# nomcu.net
KiCad netlist of a schematic drawn in EAGLE
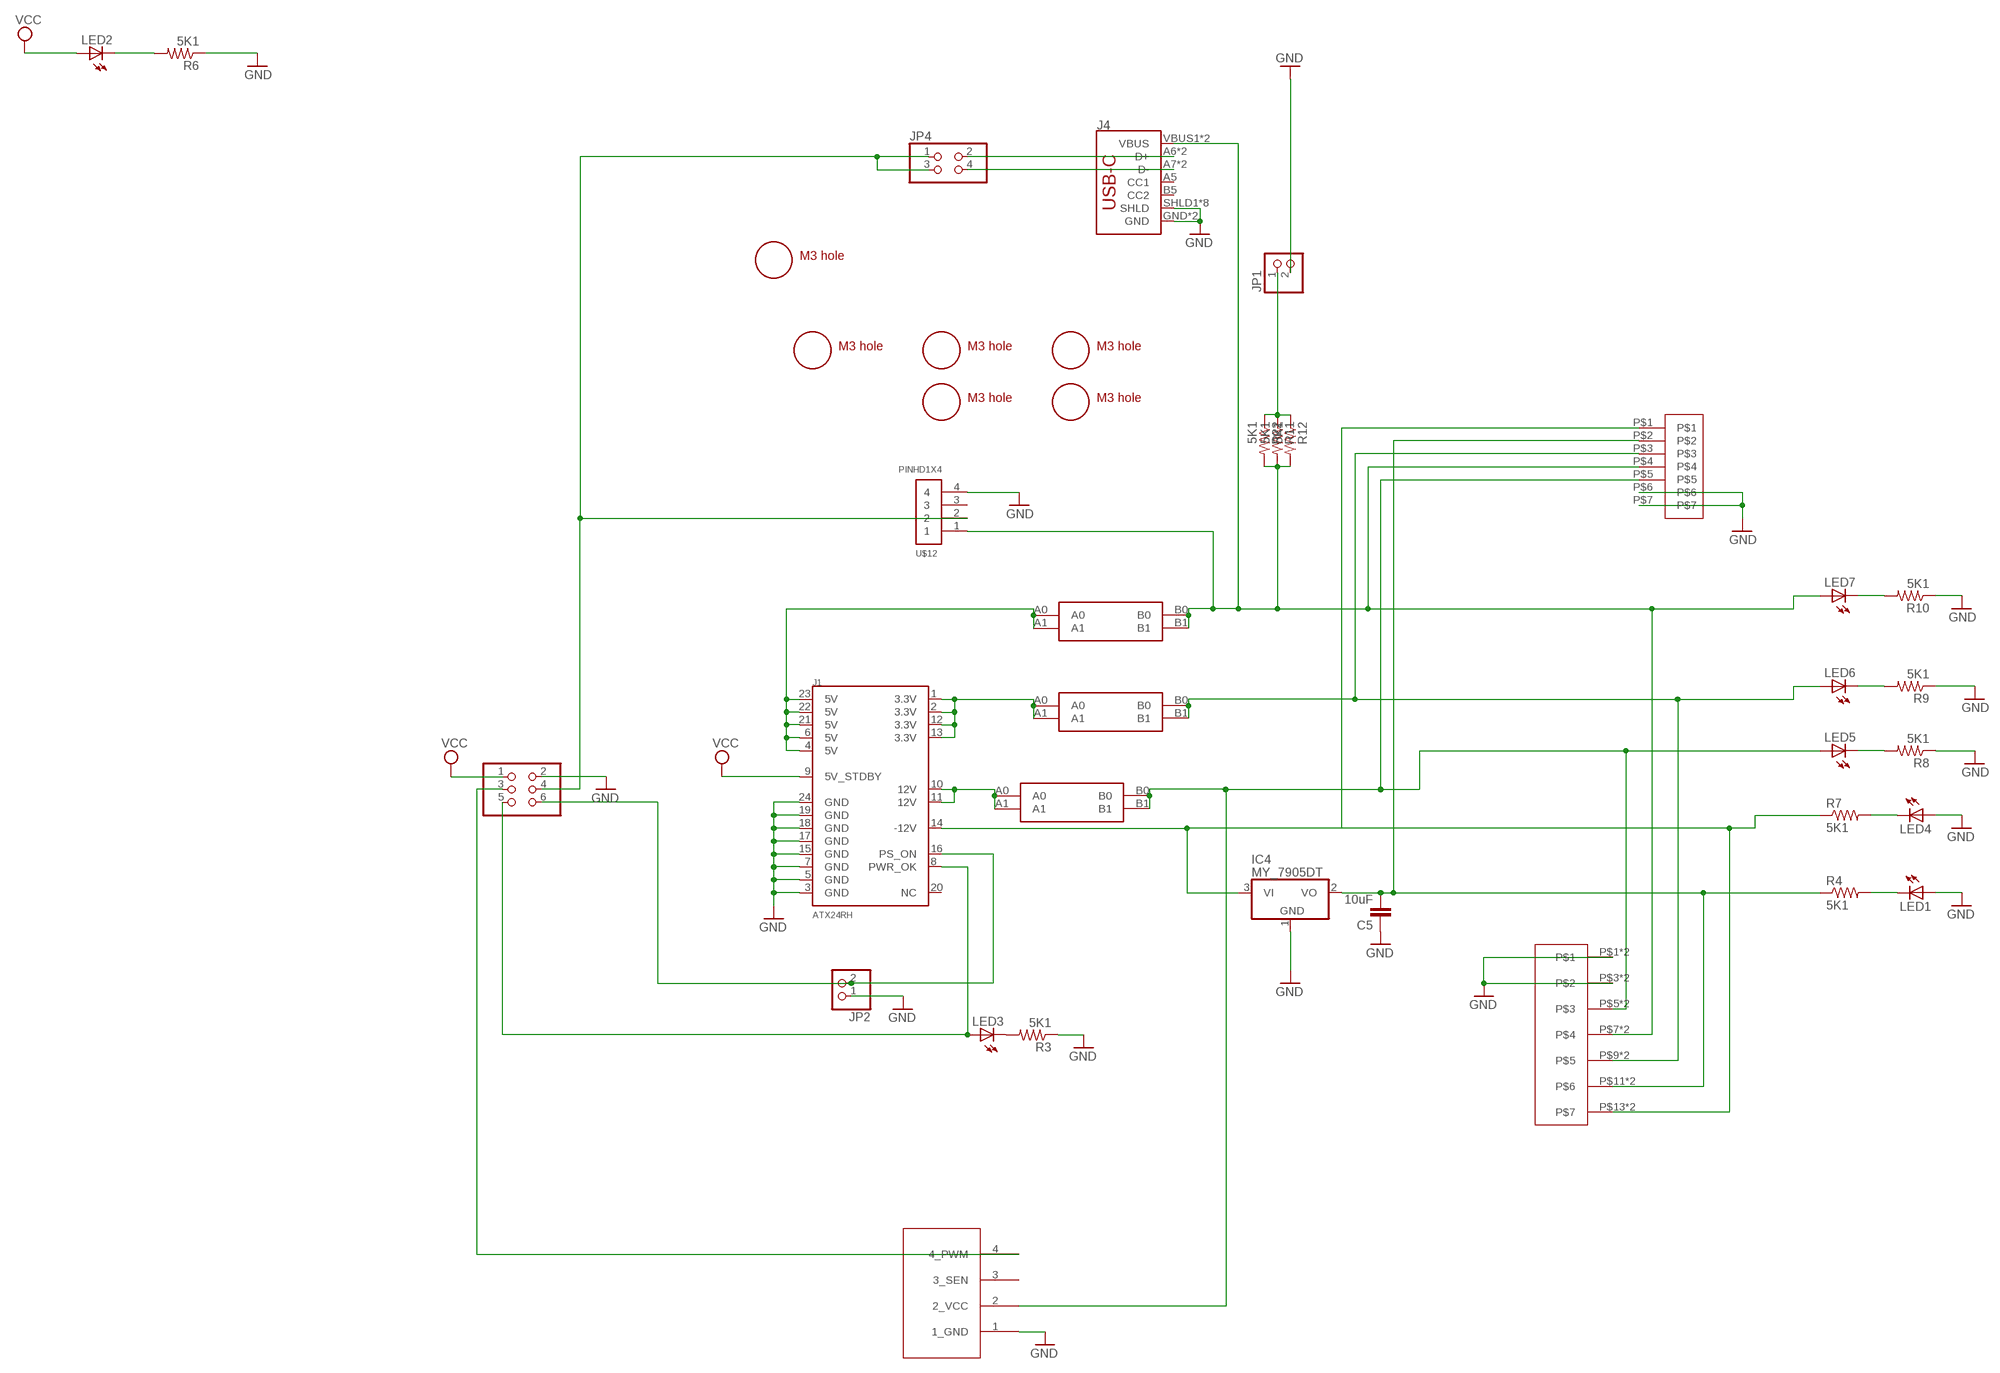
[diagram p0: schematic, sheet 1]

(export (version "E")
  (design (tool "Eeschema 10.0.6"))
  (components
    (comp (ref "C5")
      (value "10uF")
      (footprint "eagle-import:0805$1")
      (libsource (lib "eagle-import") (part "CAP0805"))
    )
    (comp (ref "IC4")
      (value "MY_7905DT")
      (footprint "eagle-import:ADAFRUIT_TO252")
      (libsource (lib "eagle-import") (part "MY_7905DT"))
    )
    (comp (ref "J1")
      (value "ATX24RH")
      (footprint "eagle-import:ATX24_RIGHT_ANGLE")
      (libsource (lib "eagle-import") (part "ATX24RH"))
    )
    (comp (ref "J4")
      (value "USB_C16PIN")
      (footprint "eagle-import:USB-C-16P")
      (libsource (lib "eagle-import") (part "USB_C16PIN"))
    )
    (comp (ref "JP1")
      (value "PINHD-1X2")
      (footprint "eagle-import:1X02")
      (libsource (lib "eagle-import") (part "PINHD-1X2"))
    )
    (comp (ref "JP2")
      (value "PINHD-1X2")
      (footprint "eagle-import:1X02")
      (libsource (lib "eagle-import") (part "PINHD-1X2"))
    )
    (comp (ref "JP3")
      (value "PINHD-2X3")
      (footprint "eagle-import:2X03")
      (libsource (lib "eagle-import") (part "PINHD-2X3"))
    )
    (comp (ref "JP4")
      (value "PINHD-2X2")
      (footprint "eagle-import:2X02")
      (libsource (lib "eagle-import") (part "PINHD-2X2"))
    )
    (comp (ref "JP8")
      (value "4PIN_FAN")
      (footprint "eagle-import:1X04")
      (libsource (lib "eagle-import") (part "4PIN_FAN"))
    )
    (comp (ref "LED1")
      (value "LEDCHIP-LED0805")
      (footprint "eagle-import:CHIP-LED0805")
      (libsource (lib "eagle-import") (part "LEDCHIP-LED0805"))
    )
    (comp (ref "LED2")
      (value "LEDCHIP-LED0805")
      (footprint "eagle-import:CHIP-LED0805")
      (libsource (lib "eagle-import") (part "LEDCHIP-LED0805"))
    )
    (comp (ref "LED3")
      (value "LEDCHIP-LED0805")
      (footprint "eagle-import:CHIP-LED0805")
      (libsource (lib "eagle-import") (part "LEDCHIP-LED0805"))
    )
    (comp (ref "LED4")
      (value "LEDCHIP-LED0805")
      (footprint "eagle-import:CHIP-LED0805")
      (libsource (lib "eagle-import") (part "LEDCHIP-LED0805"))
    )
    (comp (ref "LED5")
      (value "LEDCHIP-LED0805")
      (footprint "eagle-import:CHIP-LED0805")
      (libsource (lib "eagle-import") (part "LEDCHIP-LED0805"))
    )
    (comp (ref "LED6")
      (value "LEDCHIP-LED0805")
      (footprint "eagle-import:CHIP-LED0805")
      (libsource (lib "eagle-import") (part "LEDCHIP-LED0805"))
    )
    (comp (ref "LED7")
      (value "LEDCHIP-LED0805")
      (footprint "eagle-import:CHIP-LED0805")
      (libsource (lib "eagle-import") (part "LEDCHIP-LED0805"))
    )
    (comp (ref "R3")
      (value "5K1")
      (footprint "eagle-import:0805")
      (libsource (lib "eagle-import") (part "atx_power_control_RESISTOR0805-RES"))
    )
    (comp (ref "R4")
      (value "5K1")
      (footprint "eagle-import:0805")
      (libsource (lib "eagle-import") (part "RESISTOR0805-RES"))
    )
    (comp (ref "R6")
      (value "5K1")
      (footprint "eagle-import:0805")
      (libsource (lib "eagle-import") (part "atx_power_control_RESISTOR0805-RES"))
    )
    (comp (ref "R7")
      (value "5K1")
      (footprint "eagle-import:0805")
      (libsource (lib "eagle-import") (part "RESISTOR0805-RES"))
    )
    (comp (ref "R8")
      (value "5K1")
      (footprint "eagle-import:0805")
      (libsource (lib "eagle-import") (part "atx_power_control_RESISTOR0805-RES"))
    )
    (comp (ref "R9")
      (value "5K1")
      (footprint "eagle-import:0805")
      (libsource (lib "eagle-import") (part "atx_power_control_RESISTOR0805-RES"))
    )
    (comp (ref "R10")
      (value "5K1")
      (footprint "eagle-import:0805")
      (libsource (lib "eagle-import") (part "atx_power_control_RESISTOR0805-RES"))
    )
    (comp (ref "R11")
      (value "5K1")
      (footprint "eagle-import:0805")
      (libsource (lib "eagle-import") (part "atx_power_control_RESISTOR0805-RES"))
    )
    (comp (ref "R12")
      (value "5K1")
      (footprint "eagle-import:0805")
      (libsource (lib "eagle-import") (part "atx_power_control_RESISTOR0805-RES"))
    )
    (comp (ref "R22")
      (value "5K1")
      (footprint "eagle-import:0805")
      (libsource (lib "eagle-import") (part "atx_power_control_RESISTOR0805-RES"))
    )
    (comp (ref "U$1")
      (value "M3_MOUNTING_HOLE")
      (footprint "eagle-import:M3_MOUNTING_HOLE_PACK")
      (libsource (lib "eagle-import") (part "M3_MOUNTING_HOLE"))
    )
    (comp (ref "U$2")
      (value "M3_MOUNTING_HOLE")
      (footprint "eagle-import:M3_MOUNTING_HOLE_PACK")
      (libsource (lib "eagle-import") (part "M3_MOUNTING_HOLE"))
    )
    (comp (ref "U$3")
      (value "M3_MOUNTING_HOLE")
      (footprint "eagle-import:M3_MOUNTING_HOLE_PACK")
      (libsource (lib "eagle-import") (part "M3_MOUNTING_HOLE"))
    )
    (comp (ref "U$4")
      (value "VH396")
      (footprint "eagle-import:396_7P")
      (libsource (lib "eagle-import") (part "VH396"))
    )
    (comp (ref "U$5")
      (value "CAR_FUSE_HOLDER3IN1")
      (footprint "eagle-import:FUSE_HOLDER_3IN1")
      (libsource (lib "eagle-import") (part "CAR_FUSE_HOLDER3IN1"))
    )
    (comp (ref "U$6")
      (value "M3_MOUNTING_HOLE")
      (footprint "eagle-import:M3_MOUNTING_HOLE_PACK")
      (libsource (lib "eagle-import") (part "M3_MOUNTING_HOLE"))
    )
    (comp (ref "U$7")
      (value "CAR_FUSE_HOLDER3IN1")
      (footprint "eagle-import:FUSE_HOLDER_3IN1")
      (libsource (lib "eagle-import") (part "CAR_FUSE_HOLDER3IN1"))
    )
    (comp (ref "U$8")
      (value "CAR_FUSE_HOLDER3IN1")
      (footprint "eagle-import:FUSE_HOLDER_3IN1")
      (libsource (lib "eagle-import") (part "CAR_FUSE_HOLDER3IN1"))
    )
    (comp (ref "U$9")
      (value "DG2204R-5.0")
      (footprint "eagle-import:DG2204R")
      (libsource (lib "eagle-import") (part "DG2204R-5.0"))
    )
    (comp (ref "U$10")
      (value "M3_MOUNTING_HOLE")
      (footprint "eagle-import:M3_MOUNTING_HOLE_PACK")
      (libsource (lib "eagle-import") (part "M3_MOUNTING_HOLE"))
    )
    (comp (ref "U$11")
      (value "M3_MOUNTING_HOLE")
      (footprint "eagle-import:M3_MOUNTING_HOLE_PACK")
      (libsource (lib "eagle-import") (part "M3_MOUNTING_HOLE"))
    )
    (comp (ref "U$12")
      (value "PINHD1X4")
      (footprint "eagle-import:1X04-CLEANBIG")
      (libsource (lib "eagle-import") (part "PINHD1X4"))
    )
  )
  (nets
    (net (code "1") (name "GND") (class "Default")
      (node (ref "C5") (pin "1") (pinfunction "1_1") (pintype "passive"))
      (node (ref "IC4") (pin "1") (pinfunction "GND_1") (pintype "passive"))
      (node (ref "J1") (pin "15") (pinfunction "GND_15") (pintype "bidirectional"))
      (node (ref "J1") (pin "17") (pinfunction "GND_17") (pintype "bidirectional"))
      (node (ref "J1") (pin "18") (pinfunction "GND_18") (pintype "bidirectional"))
      (node (ref "J1") (pin "19") (pinfunction "GND_19") (pintype "bidirectional"))
      (node (ref "J1") (pin "24") (pinfunction "GND_24") (pintype "bidirectional"))
      (node (ref "J1") (pin "3") (pinfunction "GND_3") (pintype "bidirectional"))
      (node (ref "J1") (pin "5") (pinfunction "GND_5") (pintype "bidirectional"))
      (node (ref "J1") (pin "7") (pinfunction "GND_7") (pintype "bidirectional"))
      (node (ref "J4") (pin "GND") (pinfunction "GND_GND") (pintype "bidirectional"))
      (node (ref "J4") (pin "GND2") (pinfunction "GND_GND2") (pintype "bidirectional"))
      (node (ref "J4") (pin "SHLD1") (pinfunction "SHLD_SHLD1") (pintype "bidirectional"))
      (node (ref "J4") (pin "SHLD2") (pinfunction "SHLD_SHLD2") (pintype "bidirectional"))
      (node (ref "J4") (pin "SHLD3") (pinfunction "SHLD_SHLD3") (pintype "bidirectional"))
      (node (ref "J4") (pin "SHLD4") (pinfunction "SHLD_SHLD4") (pintype "bidirectional"))
      (node (ref "J4") (pin "SHLD5") (pinfunction "SHLD_SHLD5") (pintype "bidirectional"))
      (node (ref "J4") (pin "SHLD6") (pinfunction "SHLD_SHLD6") (pintype "bidirectional"))
      (node (ref "J4") (pin "SHLD7") (pinfunction "SHLD_SHLD7") (pintype "bidirectional"))
      (node (ref "J4") (pin "SHLD8") (pinfunction "SHLD_SHLD8") (pintype "bidirectional"))
      (node (ref "JP1") (pin "2") (pinfunction "2_2") (pintype "passive"))
      (node (ref "JP2") (pin "1") (pinfunction "1_1") (pintype "passive"))
      (node (ref "JP3") (pin "2") (pinfunction "2_2") (pintype "passive"))
      (node (ref "JP8") (pin "1") (pinfunction "1_GND_1") (pintype "passive"))
      (node (ref "LED1") (pin "A") (pinfunction "A_A") (pintype "passive"))
      (node (ref "LED4") (pin "A") (pinfunction "A_A") (pintype "passive"))
      (node (ref "R10") (pin "1") (pinfunction "1_1") (pintype "passive"))
      (node (ref "R3") (pin "1") (pinfunction "1_1") (pintype "passive"))
      (node (ref "R6") (pin "1") (pinfunction "1_1") (pintype "passive"))
      (node (ref "R8") (pin "1") (pinfunction "1_1") (pintype "passive"))
      (node (ref "R9") (pin "1") (pinfunction "1_1") (pintype "passive"))
      (node (ref "U$12") (pin "4") (pinfunction "4_4") (pintype "bidirectional"))
      (node (ref "U$4") (pin "P$6") (pinfunction "P$6_P$6") (pintype "bidirectional"))
      (node (ref "U$4") (pin "P$7") (pinfunction "P$7_P$7") (pintype "bidirectional"))
      (node (ref "U$9") (pin "P$1") (pinfunction "P$1_P$1") (pintype "bidirectional"))
      (node (ref "U$9") (pin "P$2") (pinfunction "P$1_P$2") (pintype "bidirectional"))
      (node (ref "U$9") (pin "P$3") (pinfunction "P$2_P$3") (pintype "bidirectional"))
      (node (ref "U$9") (pin "P$4") (pinfunction "P$2_P$4") (pintype "bidirectional"))
    )
    (net (code "2") (name "Net-(IC4-VI)") (class "Default")
      (node (ref "IC4") (pin "3") (pinfunction "VI_3") (pintype "input"))
      (node (ref "J1") (pin "14") (pinfunction "-12V_14") (pintype "bidirectional"))
      (node (ref "R7") (pin "1") (pinfunction "1_1") (pintype "passive"))
      (node (ref "U$4") (pin "P$1") (pinfunction "P$1_P$1") (pintype "bidirectional"))
      (node (ref "U$9") (pin "P$13") (pinfunction "P$7_P$13") (pintype "bidirectional"))
      (node (ref "U$9") (pin "P$14") (pinfunction "P$7_P$14") (pintype "bidirectional"))
    )
    (net (code "3") (name "Net-(IC4-VO)") (class "Default")
      (node (ref "C5") (pin "2") (pinfunction "2_2") (pintype "passive"))
      (node (ref "IC4") (pin "2") (pinfunction "VO_2") (pintype "passive"))
      (node (ref "R4") (pin "1") (pinfunction "1_1") (pintype "passive"))
      (node (ref "U$4") (pin "P$2") (pinfunction "P$2_P$2") (pintype "bidirectional"))
      (node (ref "U$9") (pin "P$11") (pinfunction "P$6_P$11") (pintype "bidirectional"))
      (node (ref "U$9") (pin "P$12") (pinfunction "P$6_P$12") (pintype "bidirectional"))
    )
    (net (code "4") (name "Net-(J1-3.3V-Pad1)") (class "Default")
      (node (ref "J1") (pin "1") (pinfunction "3.3V_1") (pintype "bidirectional"))
      (node (ref "J1") (pin "12") (pinfunction "3.3V_12") (pintype "bidirectional"))
      (node (ref "J1") (pin "13") (pinfunction "3.3V_13") (pintype "bidirectional"))
      (node (ref "J1") (pin "2") (pinfunction "3.3V_2") (pintype "bidirectional"))
      (node (ref "U$7") (pin "A0") (pinfunction "A0_A0") (pintype "bidirectional"))
      (node (ref "U$7") (pin "A1") (pinfunction "A1_A1") (pintype "bidirectional"))
    )
    (net (code "5") (name "Net-(J1-5V-Pad21)") (class "Default")
      (node (ref "J1") (pin "21") (pinfunction "5V_21") (pintype "bidirectional"))
      (node (ref "J1") (pin "22") (pinfunction "5V_22") (pintype "bidirectional"))
      (node (ref "J1") (pin "23") (pinfunction "5V_23") (pintype "bidirectional"))
      (node (ref "J1") (pin "4") (pinfunction "5V_4") (pintype "bidirectional"))
      (node (ref "J1") (pin "6") (pinfunction "5V_6") (pintype "bidirectional"))
      (node (ref "U$8") (pin "A0") (pinfunction "A0_A0") (pintype "bidirectional"))
      (node (ref "U$8") (pin "A1") (pinfunction "A1_A1") (pintype "bidirectional"))
    )
    (net (code "6") (name "Net-(J1-12V-Pad10)") (class "Default")
      (node (ref "J1") (pin "10") (pinfunction "12V_10") (pintype "bidirectional"))
      (node (ref "J1") (pin "11") (pinfunction "12V_11") (pintype "bidirectional"))
      (node (ref "U$5") (pin "A0") (pinfunction "A0_A0") (pintype "bidirectional"))
      (node (ref "U$5") (pin "A1") (pinfunction "A1_A1") (pintype "bidirectional"))
    )
    (net (code "7") (name "Net-(J1-PS_ON)") (class "Default")
      (node (ref "J1") (pin "16") (pinfunction "PS_ON_16") (pintype "bidirectional"))
      (node (ref "JP2") (pin "2") (pinfunction "2_2") (pintype "passive"))
      (node (ref "JP3") (pin "6") (pinfunction "6_6") (pintype "passive"))
    )
    (net (code "8") (name "Net-(J1-PWR_OK)") (class "Default")
      (node (ref "J1") (pin "8") (pinfunction "PWR_OK_8") (pintype "bidirectional"))
      (node (ref "JP3") (pin "5") (pinfunction "5_5") (pintype "passive"))
      (node (ref "LED3") (pin "A") (pinfunction "A_A") (pintype "passive"))
    )
    (net (code "9") (name "Net-(J4-D+-PadA6)") (class "Default")
      (node (ref "J4") (pin "A6") (pinfunction "D+_A6") (pintype "bidirectional"))
      (node (ref "J4") (pin "B6") (pinfunction "D+_B6") (pintype "bidirectional"))
      (node (ref "JP4") (pin "2") (pinfunction "2_2") (pintype "passive"))
    )
    (net (code "10") (name "Net-(J4-D--PadA7)") (class "Default")
      (node (ref "J4") (pin "A7") (pinfunction "D-_A7") (pintype "bidirectional"))
      (node (ref "J4") (pin "B7") (pinfunction "D-_B7") (pintype "bidirectional"))
      (node (ref "JP4") (pin "4") (pinfunction "4_4") (pintype "passive"))
    )
    (net (code "11") (name "Net-(J4-VBUS-PadVBUS1)") (class "Default")
      (node (ref "J4") (pin "VBUS1") (pinfunction "VBUS_VBUS1") (pintype "bidirectional"))
      (node (ref "J4") (pin "VBUS2") (pinfunction "VBUS_VBUS2") (pintype "bidirectional"))
      (node (ref "LED7") (pin "A") (pinfunction "A_A") (pintype "passive"))
      (node (ref "R11") (pin "2") (pinfunction "2_2") (pintype "passive"))
      (node (ref "R12") (pin "2") (pinfunction "2_2") (pintype "passive"))
      (node (ref "R22") (pin "2") (pinfunction "2_2") (pintype "passive"))
      (node (ref "U$12") (pin "1") (pinfunction "1_1") (pintype "bidirectional"))
      (node (ref "U$4") (pin "P$4") (pinfunction "P$4_P$4") (pintype "bidirectional"))
      (node (ref "U$8") (pin "B0") (pinfunction "B0_B0") (pintype "bidirectional"))
      (node (ref "U$8") (pin "B1") (pinfunction "B1_B1") (pintype "bidirectional"))
      (node (ref "U$9") (pin "P$7") (pinfunction "P$4_P$7") (pintype "bidirectional"))
      (node (ref "U$9") (pin "P$8") (pinfunction "P$4_P$8") (pintype "bidirectional"))
    )
    (net (code "12") (name "Net-(JP1-Pad1)") (class "Default")
      (node (ref "JP1") (pin "1") (pinfunction "1_1") (pintype "passive"))
      (node (ref "R11") (pin "1") (pinfunction "1_1") (pintype "passive"))
      (node (ref "R12") (pin "1") (pinfunction "1_1") (pintype "passive"))
      (node (ref "R22") (pin "1") (pinfunction "1_1") (pintype "passive"))
    )
    (net (code "13") (name "Net-(JP3-Pad4)") (class "Default")
      (node (ref "JP3") (pin "4") (pinfunction "4_4") (pintype "passive"))
      (node (ref "JP4") (pin "1") (pinfunction "1_1") (pintype "passive"))
      (node (ref "JP4") (pin "3") (pinfunction "3_3") (pintype "passive"))
      (node (ref "U$12") (pin "2") (pinfunction "2_2") (pintype "bidirectional"))
    )
    (net (code "14") (name "Net-(JP8-2_VCC)") (class "Default")
      (node (ref "JP8") (pin "2") (pinfunction "2_VCC_2") (pintype "passive"))
      (node (ref "LED5") (pin "A") (pinfunction "A_A") (pintype "passive"))
      (node (ref "U$4") (pin "P$5") (pinfunction "P$5_P$5") (pintype "bidirectional"))
      (node (ref "U$5") (pin "B0") (pinfunction "B0_B0") (pintype "bidirectional"))
      (node (ref "U$5") (pin "B1") (pinfunction "B1_B1") (pintype "bidirectional"))
      (node (ref "U$9") (pin "P$5") (pinfunction "P$3_P$5") (pintype "bidirectional"))
      (node (ref "U$9") (pin "P$6") (pinfunction "P$3_P$6") (pintype "bidirectional"))
    )
    (net (code "15") (name "Net-(JP8-4_PWM)") (class "Default")
      (node (ref "JP3") (pin "3") (pinfunction "3_3") (pintype "passive"))
      (node (ref "JP8") (pin "4") (pinfunction "4_PWM_4") (pintype "passive"))
    )
    (net (code "16") (name "Net-(LED1-PadC)") (class "Default")
      (node (ref "LED1") (pin "C") (pinfunction "C_C") (pintype "passive"))
      (node (ref "R4") (pin "2") (pinfunction "2_2") (pintype "passive"))
    )
    (net (code "17") (name "Net-(LED2-PadC)") (class "Default")
      (node (ref "LED2") (pin "C") (pinfunction "C_C") (pintype "passive"))
      (node (ref "R6") (pin "2") (pinfunction "2_2") (pintype "passive"))
    )
    (net (code "18") (name "Net-(LED3-PadC)") (class "Default")
      (node (ref "LED3") (pin "C") (pinfunction "C_C") (pintype "passive"))
      (node (ref "R3") (pin "2") (pinfunction "2_2") (pintype "passive"))
    )
    (net (code "19") (name "Net-(LED4-PadC)") (class "Default")
      (node (ref "LED4") (pin "C") (pinfunction "C_C") (pintype "passive"))
      (node (ref "R7") (pin "2") (pinfunction "2_2") (pintype "passive"))
    )
    (net (code "20") (name "Net-(LED5-PadC)") (class "Default")
      (node (ref "LED5") (pin "C") (pinfunction "C_C") (pintype "passive"))
      (node (ref "R8") (pin "2") (pinfunction "2_2") (pintype "passive"))
    )
    (net (code "21") (name "Net-(LED6-PadA)") (class "Default")
      (node (ref "LED6") (pin "A") (pinfunction "A_A") (pintype "passive"))
      (node (ref "U$4") (pin "P$3") (pinfunction "P$3_P$3") (pintype "bidirectional"))
      (node (ref "U$7") (pin "B0") (pinfunction "B0_B0") (pintype "bidirectional"))
      (node (ref "U$7") (pin "B1") (pinfunction "B1_B1") (pintype "bidirectional"))
      (node (ref "U$9") (pin "P$10") (pinfunction "P$5_P$10") (pintype "bidirectional"))
      (node (ref "U$9") (pin "P$9") (pinfunction "P$5_P$9") (pintype "bidirectional"))
    )
    (net (code "22") (name "Net-(LED6-PadC)") (class "Default")
      (node (ref "LED6") (pin "C") (pinfunction "C_C") (pintype "passive"))
      (node (ref "R9") (pin "2") (pinfunction "2_2") (pintype "passive"))
    )
    (net (code "23") (name "Net-(LED7-PadC)") (class "Default")
      (node (ref "LED7") (pin "C") (pinfunction "C_C") (pintype "passive"))
      (node (ref "R10") (pin "2") (pinfunction "2_2") (pintype "passive"))
    )
    (net (code "24") (name "VCC") (class "Default")
      (node (ref "J1") (pin "9") (pinfunction "5V_STDBY_9") (pintype "bidirectional"))
      (node (ref "JP3") (pin "1") (pinfunction "1_1") (pintype "passive"))
      (node (ref "LED2") (pin "A") (pinfunction "A_A") (pintype "passive"))
    )
    (net (code "25") (name "unconnected-(J1-NC-Pad20)") (class "Default")
      (node (ref "J1") (pin "20") (pinfunction "NC_20") (pintype "bidirectional"))
    )
    (net (code "26") (name "unconnected-(J4-CC1-PadA5)") (class "Default")
      (node (ref "J4") (pin "A5") (pinfunction "CC1_A5") (pintype "bidirectional"))
    )
    (net (code "27") (name "unconnected-(J4-CC2-PadB5)") (class "Default")
      (node (ref "J4") (pin "B5") (pinfunction "CC2_B5") (pintype "bidirectional"))
    )
    (net (code "28") (name "unconnected-(JP8-3_SEN-Pad3)") (class "Default")
      (node (ref "JP8") (pin "3") (pinfunction "3_SEN_3") (pintype "passive"))
    )
    (net (code "29") (name "unconnected-(U$12-Pad3)") (class "Default")
      (node (ref "U$12") (pin "3") (pinfunction "3_3") (pintype "bidirectional"))
    )
  )
)
